# SmartGarden.net
KiCad netlist of a schematic drawn in EAGLE
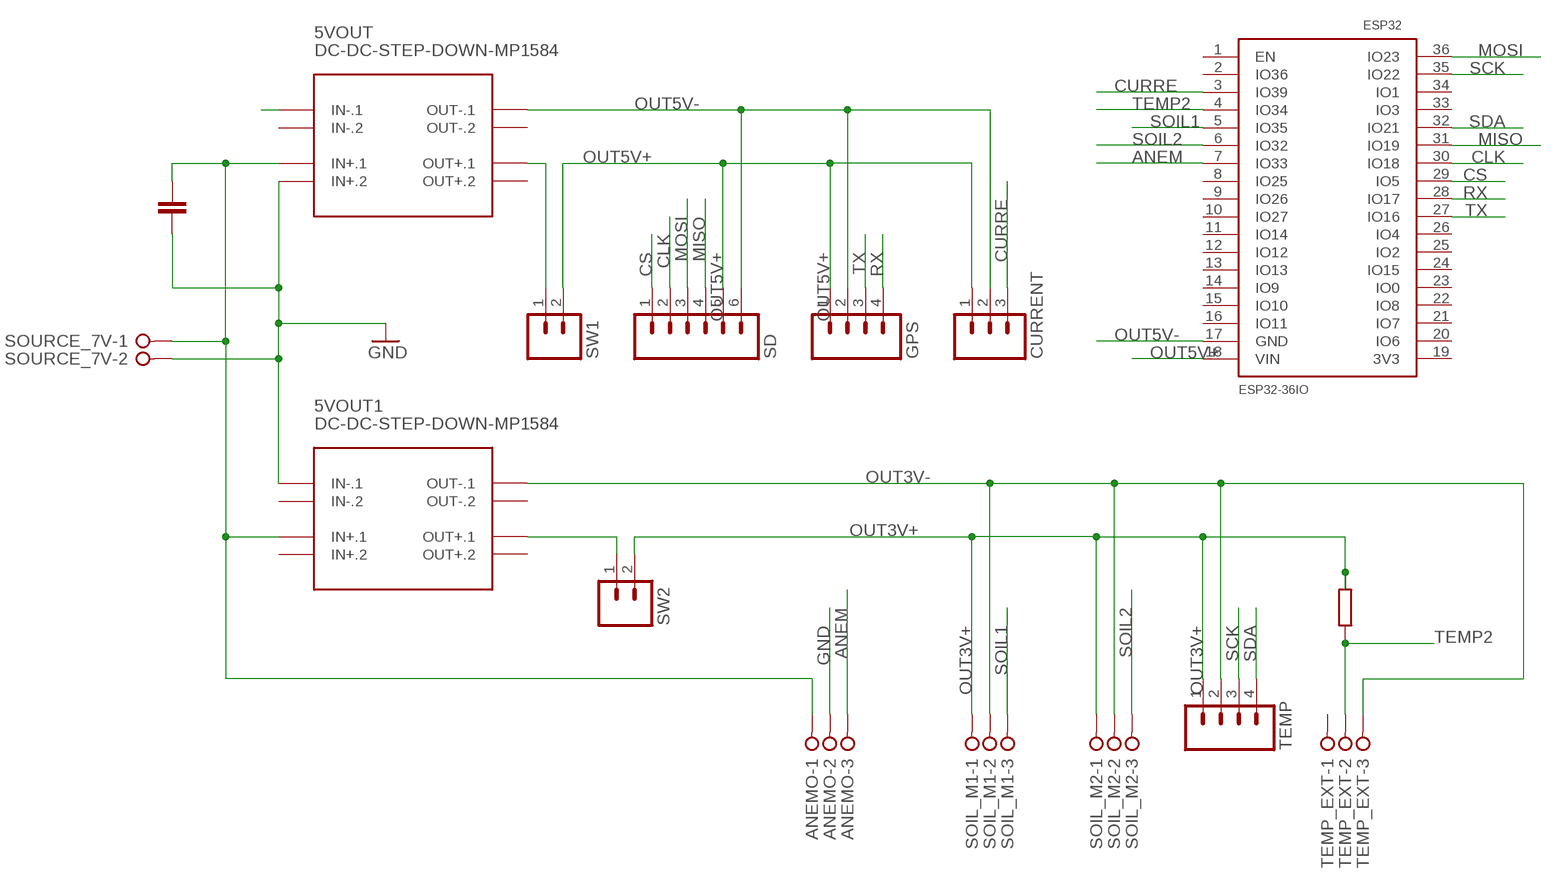
[diagram p0: schematic, sheet 1]

(export (version "E")
  (design (tool "Eeschema 10.0.6"))
  (components
    (comp (ref "5VOUT")
      (value "DC-DC-STEP-DOWN-MP1584")
      (footprint "eagle-import:DC-DC-STEP-DOWN-MP1584")
      (libsource (lib "eagle-import") (part "DC-DC-STEP-DOWN-MP1584"))
    )
    (comp (ref "5VOUT1")
      (value "DC-DC-STEP-DOWN-MP1584")
      (footprint "eagle-import:DC-DC-STEP-DOWN-MP1584")
      (libsource (lib "eagle-import") (part "DC-DC-STEP-DOWN-MP1584"))
    )
    (comp (ref "ANEMO")
      (value "W237-3E")
      (footprint "eagle-import:W237-3E")
      (libsource (lib "eagle-import") (part "W237-3E"))
    )
    (comp (ref "C0")
      (value "C-EU025-025X050")
      (footprint "eagle-import:C025-025X050")
      (libsource (lib "eagle-import") (part "C-EU025-025X050"))
    )
    (comp (ref "CURRENT")
      (value "M03")
      (footprint "eagle-import:03P")
      (libsource (lib "eagle-import") (part "M03"))
    )
    (comp (ref "ESP32")
      (value "ESP32-36IO")
      (footprint "eagle-import:ESP32-36-GPIO")
      (libsource (lib "eagle-import") (part "ESP32-36IO"))
    )
    (comp (ref "GPS")
      (value "M04")
      (footprint "eagle-import:04P")
      (libsource (lib "eagle-import") (part "M04"))
    )
    (comp (ref "R1")
      (value "R-EU_0204/7")
      (footprint "eagle-import:0204_7")
      (libsource (lib "eagle-import") (part "R-EU_0204/7"))
    )
    (comp (ref "SD")
      (value "M06")
      (footprint "eagle-import:06P")
      (libsource (lib "eagle-import") (part "M06"))
    )
    (comp (ref "SOIL_M1")
      (value "W237-3E")
      (footprint "eagle-import:W237-3E")
      (libsource (lib "eagle-import") (part "W237-3E"))
    )
    (comp (ref "SOIL_M2")
      (value "W237-3E")
      (footprint "eagle-import:W237-3E")
      (libsource (lib "eagle-import") (part "W237-3E"))
    )
    (comp (ref "SOURCE_7V")
      (value "W237-02P")
      (footprint "eagle-import:W237-132")
      (libsource (lib "eagle-import") (part "W237-02P"))
    )
    (comp (ref "SW1")
      (value "M02")
      (footprint "eagle-import:02P")
      (libsource (lib "eagle-import") (part "M02"))
    )
    (comp (ref "SW2")
      (value "M02")
      (footprint "eagle-import:02P")
      (libsource (lib "eagle-import") (part "M02"))
    )
    (comp (ref "TEMP")
      (value "M04")
      (footprint "eagle-import:04P")
      (libsource (lib "eagle-import") (part "M04"))
    )
    (comp (ref "TEMP_EXT")
      (value "W237-3E")
      (footprint "eagle-import:W237-3E")
      (libsource (lib "eagle-import") (part "W237-3E"))
    )
  )
  (nets
    (net (code "1") (name "/ANEM") (class "Default")
      (node (ref "ANEMO") (pin "3") (pinfunction "KL_3") (pintype "passive"))
      (node (ref "ESP32") (pin "7") (pinfunction "IO33_7") (pintype "bidirectional"))
    )
    (net (code "2") (name "/CLK") (class "Default")
      (node (ref "ESP32") (pin "30") (pinfunction "IO18_30") (pintype "bidirectional"))
      (node (ref "SD") (pin "2") (pinfunction "2_2") (pintype "passive"))
    )
    (net (code "3") (name "/CS") (class "Default")
      (node (ref "ESP32") (pin "29") (pinfunction "IO5_29") (pintype "bidirectional"))
      (node (ref "SD") (pin "1") (pinfunction "1_1") (pintype "passive"))
    )
    (net (code "4") (name "/CURRE") (class "Default")
      (node (ref "CURRENT") (pin "3") (pinfunction "3_3") (pintype "passive"))
      (node (ref "ESP32") (pin "3") (pinfunction "IO39_3") (pintype "bidirectional"))
    )
    (net (code "5") (name "/MISO") (class "Default")
      (node (ref "ESP32") (pin "31") (pinfunction "IO19_31") (pintype "bidirectional"))
      (node (ref "SD") (pin "4") (pinfunction "4_4") (pintype "passive"))
    )
    (net (code "6") (name "/MOSI") (class "Default")
      (node (ref "ESP32") (pin "36") (pinfunction "IO23_36") (pintype "bidirectional"))
      (node (ref "SD") (pin "3") (pinfunction "3_3") (pintype "passive"))
    )
    (net (code "7") (name "/OUT3V+") (class "Default")
      (node (ref "R1") (pin "2") (pinfunction "2_2") (pintype "passive"))
      (node (ref "SOIL_M1") (pin "1") (pinfunction "KL_1") (pintype "passive"))
      (node (ref "SOIL_M2") (pin "1") (pinfunction "KL_1") (pintype "passive"))
      (node (ref "SW2") (pin "2") (pinfunction "2_2") (pintype "passive"))
      (node (ref "TEMP") (pin "1") (pinfunction "1_1") (pintype "passive"))
    )
    (net (code "8") (name "/OUT3V-") (class "Default")
      (node (ref "5VOUT1") (pin "OUT-.1") (pinfunction "OUT-.1_OUT-.1") (pintype "bidirectional"))
      (node (ref "SOIL_M1") (pin "2") (pinfunction "KL_2") (pintype "passive"))
      (node (ref "SOIL_M2") (pin "2") (pinfunction "KL_2") (pintype "passive"))
      (node (ref "TEMP") (pin "2") (pinfunction "2_2") (pintype "passive"))
      (node (ref "TEMP_EXT") (pin "3") (pinfunction "KL_3") (pintype "passive"))
    )
    (net (code "9") (name "/OUT5V+") (class "Default")
      (node (ref "CURRENT") (pin "1") (pinfunction "1_1") (pintype "passive"))
      (node (ref "ESP32") (pin "18") (pinfunction "VIN_18") (pintype "bidirectional"))
      (node (ref "GPS") (pin "1") (pinfunction "1_1") (pintype "passive"))
      (node (ref "SD") (pin "5") (pinfunction "5_5") (pintype "passive"))
      (node (ref "SW1") (pin "2") (pinfunction "2_2") (pintype "passive"))
    )
    (net (code "10") (name "/OUT5V-") (class "Default")
      (node (ref "5VOUT") (pin "OUT-.1") (pinfunction "OUT-.1_OUT-.1") (pintype "bidirectional"))
      (node (ref "CURRENT") (pin "2") (pinfunction "2_2") (pintype "passive"))
      (node (ref "ESP32") (pin "17") (pinfunction "GND_17") (pintype "bidirectional"))
      (node (ref "GPS") (pin "2") (pinfunction "2_2") (pintype "passive"))
      (node (ref "SD") (pin "6") (pinfunction "6_6") (pintype "passive"))
    )
    (net (code "11") (name "/RX") (class "Default")
      (node (ref "ESP32") (pin "28") (pinfunction "IO17_28") (pintype "bidirectional"))
      (node (ref "GPS") (pin "4") (pinfunction "4_4") (pintype "passive"))
    )
    (net (code "12") (name "/SCK") (class "Default")
      (node (ref "ESP32") (pin "35") (pinfunction "IO22_35") (pintype "bidirectional"))
      (node (ref "TEMP") (pin "3") (pinfunction "3_3") (pintype "passive"))
    )
    (net (code "13") (name "/SDA") (class "Default")
      (node (ref "ESP32") (pin "32") (pinfunction "IO21_32") (pintype "bidirectional"))
      (node (ref "TEMP") (pin "4") (pinfunction "4_4") (pintype "passive"))
    )
    (net (code "14") (name "/SOIL1") (class "Default")
      (node (ref "ESP32") (pin "5") (pinfunction "IO35_5") (pintype "bidirectional"))
      (node (ref "SOIL_M1") (pin "3") (pinfunction "KL_3") (pintype "passive"))
    )
    (net (code "15") (name "/SOIL2") (class "Default")
      (node (ref "ESP32") (pin "6") (pinfunction "IO32_6") (pintype "bidirectional"))
      (node (ref "SOIL_M2") (pin "3") (pinfunction "KL_3") (pintype "passive"))
    )
    (net (code "16") (name "/TEMP2") (class "Default")
      (node (ref "ESP32") (pin "4") (pinfunction "IO34_4") (pintype "bidirectional"))
      (node (ref "R1") (pin "1") (pinfunction "1_1") (pintype "passive"))
      (node (ref "TEMP_EXT") (pin "2") (pinfunction "KL_2") (pintype "passive"))
    )
    (net (code "17") (name "/TX") (class "Default")
      (node (ref "ESP32") (pin "27") (pinfunction "IO16_27") (pintype "bidirectional"))
      (node (ref "GPS") (pin "3") (pinfunction "3_3") (pintype "passive"))
    )
    (net (code "18") (name "GND") (class "Default")
      (node (ref "5VOUT") (pin "IN+.2") (pinfunction "IN+.2_IN+.2") (pintype "bidirectional"))
      (node (ref "5VOUT1") (pin "IN-.1") (pinfunction "IN-.1_IN-.1") (pintype "bidirectional"))
      (node (ref "ANEMO") (pin "2") (pinfunction "KL_2") (pintype "passive"))
      (node (ref "C0") (pin "2") (pinfunction "2_2") (pintype "passive"))
      (node (ref "SOURCE_7V") (pin "2") (pinfunction "KL_2") (pintype "passive"))
    )
    (net (code "19") (name "Net-(5VOUT-PadOUT+.1)") (class "Default")
      (node (ref "5VOUT") (pin "OUT+.1") (pinfunction "OUT+.1_OUT+.1") (pintype "bidirectional"))
      (node (ref "SW1") (pin "1") (pinfunction "1_1") (pintype "passive"))
    )
    (net (code "20") (name "Net-(5VOUT1-PadOUT+.1)") (class "Default")
      (node (ref "5VOUT1") (pin "OUT+.1") (pinfunction "OUT+.1_OUT+.1") (pintype "bidirectional"))
      (node (ref "SW2") (pin "1") (pinfunction "1_1") (pintype "passive"))
    )
    (net (code "21") (name "Net-(ANEMOA-KL)") (class "Default")
      (node (ref "5VOUT") (pin "IN+.1") (pinfunction "IN+.1_IN+.1") (pintype "bidirectional"))
      (node (ref "5VOUT1") (pin "IN+.1") (pinfunction "IN+.1_IN+.1") (pintype "bidirectional"))
      (node (ref "ANEMO") (pin "1") (pinfunction "KL_1") (pintype "passive"))
      (node (ref "C0") (pin "1") (pinfunction "1_1") (pintype "passive"))
      (node (ref "SOURCE_7V") (pin "1") (pinfunction "KL_1") (pintype "passive"))
    )
    (net (code "22") (name "unconnected-(5VOUT-PadIN-.1)") (class "Default")
      (node (ref "5VOUT") (pin "IN-.1") (pinfunction "IN-.1_IN-.1") (pintype "bidirectional"))
    )
    (net (code "23") (name "unconnected-(5VOUT-PadIN-.2)") (class "Default")
      (node (ref "5VOUT") (pin "IN-.2") (pinfunction "IN-.2_IN-.2") (pintype "bidirectional"))
    )
    (net (code "24") (name "unconnected-(5VOUT-PadOUT+.2)") (class "Default")
      (node (ref "5VOUT") (pin "OUT+.2") (pinfunction "OUT+.2_OUT+.2") (pintype "bidirectional"))
    )
    (net (code "25") (name "unconnected-(5VOUT-PadOUT-.2)") (class "Default")
      (node (ref "5VOUT") (pin "OUT-.2") (pinfunction "OUT-.2_OUT-.2") (pintype "bidirectional"))
    )
    (net (code "26") (name "unconnected-(5VOUT1-PadIN+.2)") (class "Default")
      (node (ref "5VOUT1") (pin "IN+.2") (pinfunction "IN+.2_IN+.2") (pintype "bidirectional"))
    )
    (net (code "27") (name "unconnected-(5VOUT1-PadIN-.2)") (class "Default")
      (node (ref "5VOUT1") (pin "IN-.2") (pinfunction "IN-.2_IN-.2") (pintype "bidirectional"))
    )
    (net (code "28") (name "unconnected-(5VOUT1-PadOUT+.2)") (class "Default")
      (node (ref "5VOUT1") (pin "OUT+.2") (pinfunction "OUT+.2_OUT+.2") (pintype "bidirectional"))
    )
    (net (code "29") (name "unconnected-(5VOUT1-PadOUT-.2)") (class "Default")
      (node (ref "5VOUT1") (pin "OUT-.2") (pinfunction "OUT-.2_OUT-.2") (pintype "bidirectional"))
    )
    (net (code "30") (name "unconnected-(ESP32-3V3-Pad19)") (class "Default")
      (node (ref "ESP32") (pin "19") (pinfunction "3V3_19") (pintype "bidirectional"))
    )
    (net (code "31") (name "unconnected-(ESP32-EN-Pad1)") (class "Default")
      (node (ref "ESP32") (pin "1") (pinfunction "EN_1") (pintype "bidirectional"))
    )
    (net (code "32") (name "unconnected-(ESP32-IO0-Pad23)") (class "Default")
      (node (ref "ESP32") (pin "23") (pinfunction "IO0_23") (pintype "bidirectional"))
    )
    (net (code "33") (name "unconnected-(ESP32-IO1-Pad34)") (class "Default")
      (node (ref "ESP32") (pin "34") (pinfunction "IO1_34") (pintype "bidirectional"))
    )
    (net (code "34") (name "unconnected-(ESP32-IO2-Pad25)") (class "Default")
      (node (ref "ESP32") (pin "25") (pinfunction "IO2_25") (pintype "bidirectional"))
    )
    (net (code "35") (name "unconnected-(ESP32-IO3-Pad33)") (class "Default")
      (node (ref "ESP32") (pin "33") (pinfunction "IO3_33") (pintype "bidirectional"))
    )
    (net (code "36") (name "unconnected-(ESP32-IO4-Pad26)") (class "Default")
      (node (ref "ESP32") (pin "26") (pinfunction "IO4_26") (pintype "bidirectional"))
    )
    (net (code "37") (name "unconnected-(ESP32-IO6-Pad20)") (class "Default")
      (node (ref "ESP32") (pin "20") (pinfunction "IO6_20") (pintype "bidirectional"))
    )
    (net (code "38") (name "unconnected-(ESP32-IO7-Pad21)") (class "Default")
      (node (ref "ESP32") (pin "21") (pinfunction "IO7_21") (pintype "bidirectional"))
    )
    (net (code "39") (name "unconnected-(ESP32-IO8-Pad22)") (class "Default")
      (node (ref "ESP32") (pin "22") (pinfunction "IO8_22") (pintype "bidirectional"))
    )
    (net (code "40") (name "unconnected-(ESP32-IO9-Pad14)") (class "Default")
      (node (ref "ESP32") (pin "14") (pinfunction "IO9_14") (pintype "bidirectional"))
    )
    (net (code "41") (name "unconnected-(ESP32-IO10-Pad15)") (class "Default")
      (node (ref "ESP32") (pin "15") (pinfunction "IO10_15") (pintype "bidirectional"))
    )
    (net (code "42") (name "unconnected-(ESP32-IO11-Pad16)") (class "Default")
      (node (ref "ESP32") (pin "16") (pinfunction "IO11_16") (pintype "bidirectional"))
    )
    (net (code "43") (name "unconnected-(ESP32-IO12-Pad12)") (class "Default")
      (node (ref "ESP32") (pin "12") (pinfunction "IO12_12") (pintype "bidirectional"))
    )
    (net (code "44") (name "unconnected-(ESP32-IO13-Pad13)") (class "Default")
      (node (ref "ESP32") (pin "13") (pinfunction "IO13_13") (pintype "bidirectional"))
    )
    (net (code "45") (name "unconnected-(ESP32-IO14-Pad11)") (class "Default")
      (node (ref "ESP32") (pin "11") (pinfunction "IO14_11") (pintype "bidirectional"))
    )
    (net (code "46") (name "unconnected-(ESP32-IO15-Pad24)") (class "Default")
      (node (ref "ESP32") (pin "24") (pinfunction "IO15_24") (pintype "bidirectional"))
    )
    (net (code "47") (name "unconnected-(ESP32-IO25-Pad8)") (class "Default")
      (node (ref "ESP32") (pin "8") (pinfunction "IO25_8") (pintype "bidirectional"))
    )
    (net (code "48") (name "unconnected-(ESP32-IO26-Pad9)") (class "Default")
      (node (ref "ESP32") (pin "9") (pinfunction "IO26_9") (pintype "bidirectional"))
    )
    (net (code "49") (name "unconnected-(ESP32-IO27-Pad10)") (class "Default")
      (node (ref "ESP32") (pin "10") (pinfunction "IO27_10") (pintype "bidirectional"))
    )
    (net (code "50") (name "unconnected-(ESP32-IO36-Pad2)") (class "Default")
      (node (ref "ESP32") (pin "2") (pinfunction "IO36_2") (pintype "bidirectional"))
    )
    (net (code "51") (name "unconnected-(TEMP_EXTA-KL-Pad1)") (class "Default")
      (node (ref "TEMP_EXT") (pin "1") (pinfunction "KL_1") (pintype "passive"))
    )
  )
)
